# Riden_Wi-Fi_V1_1.net
KiCad netlist of a schematic drawn in EasyEDA
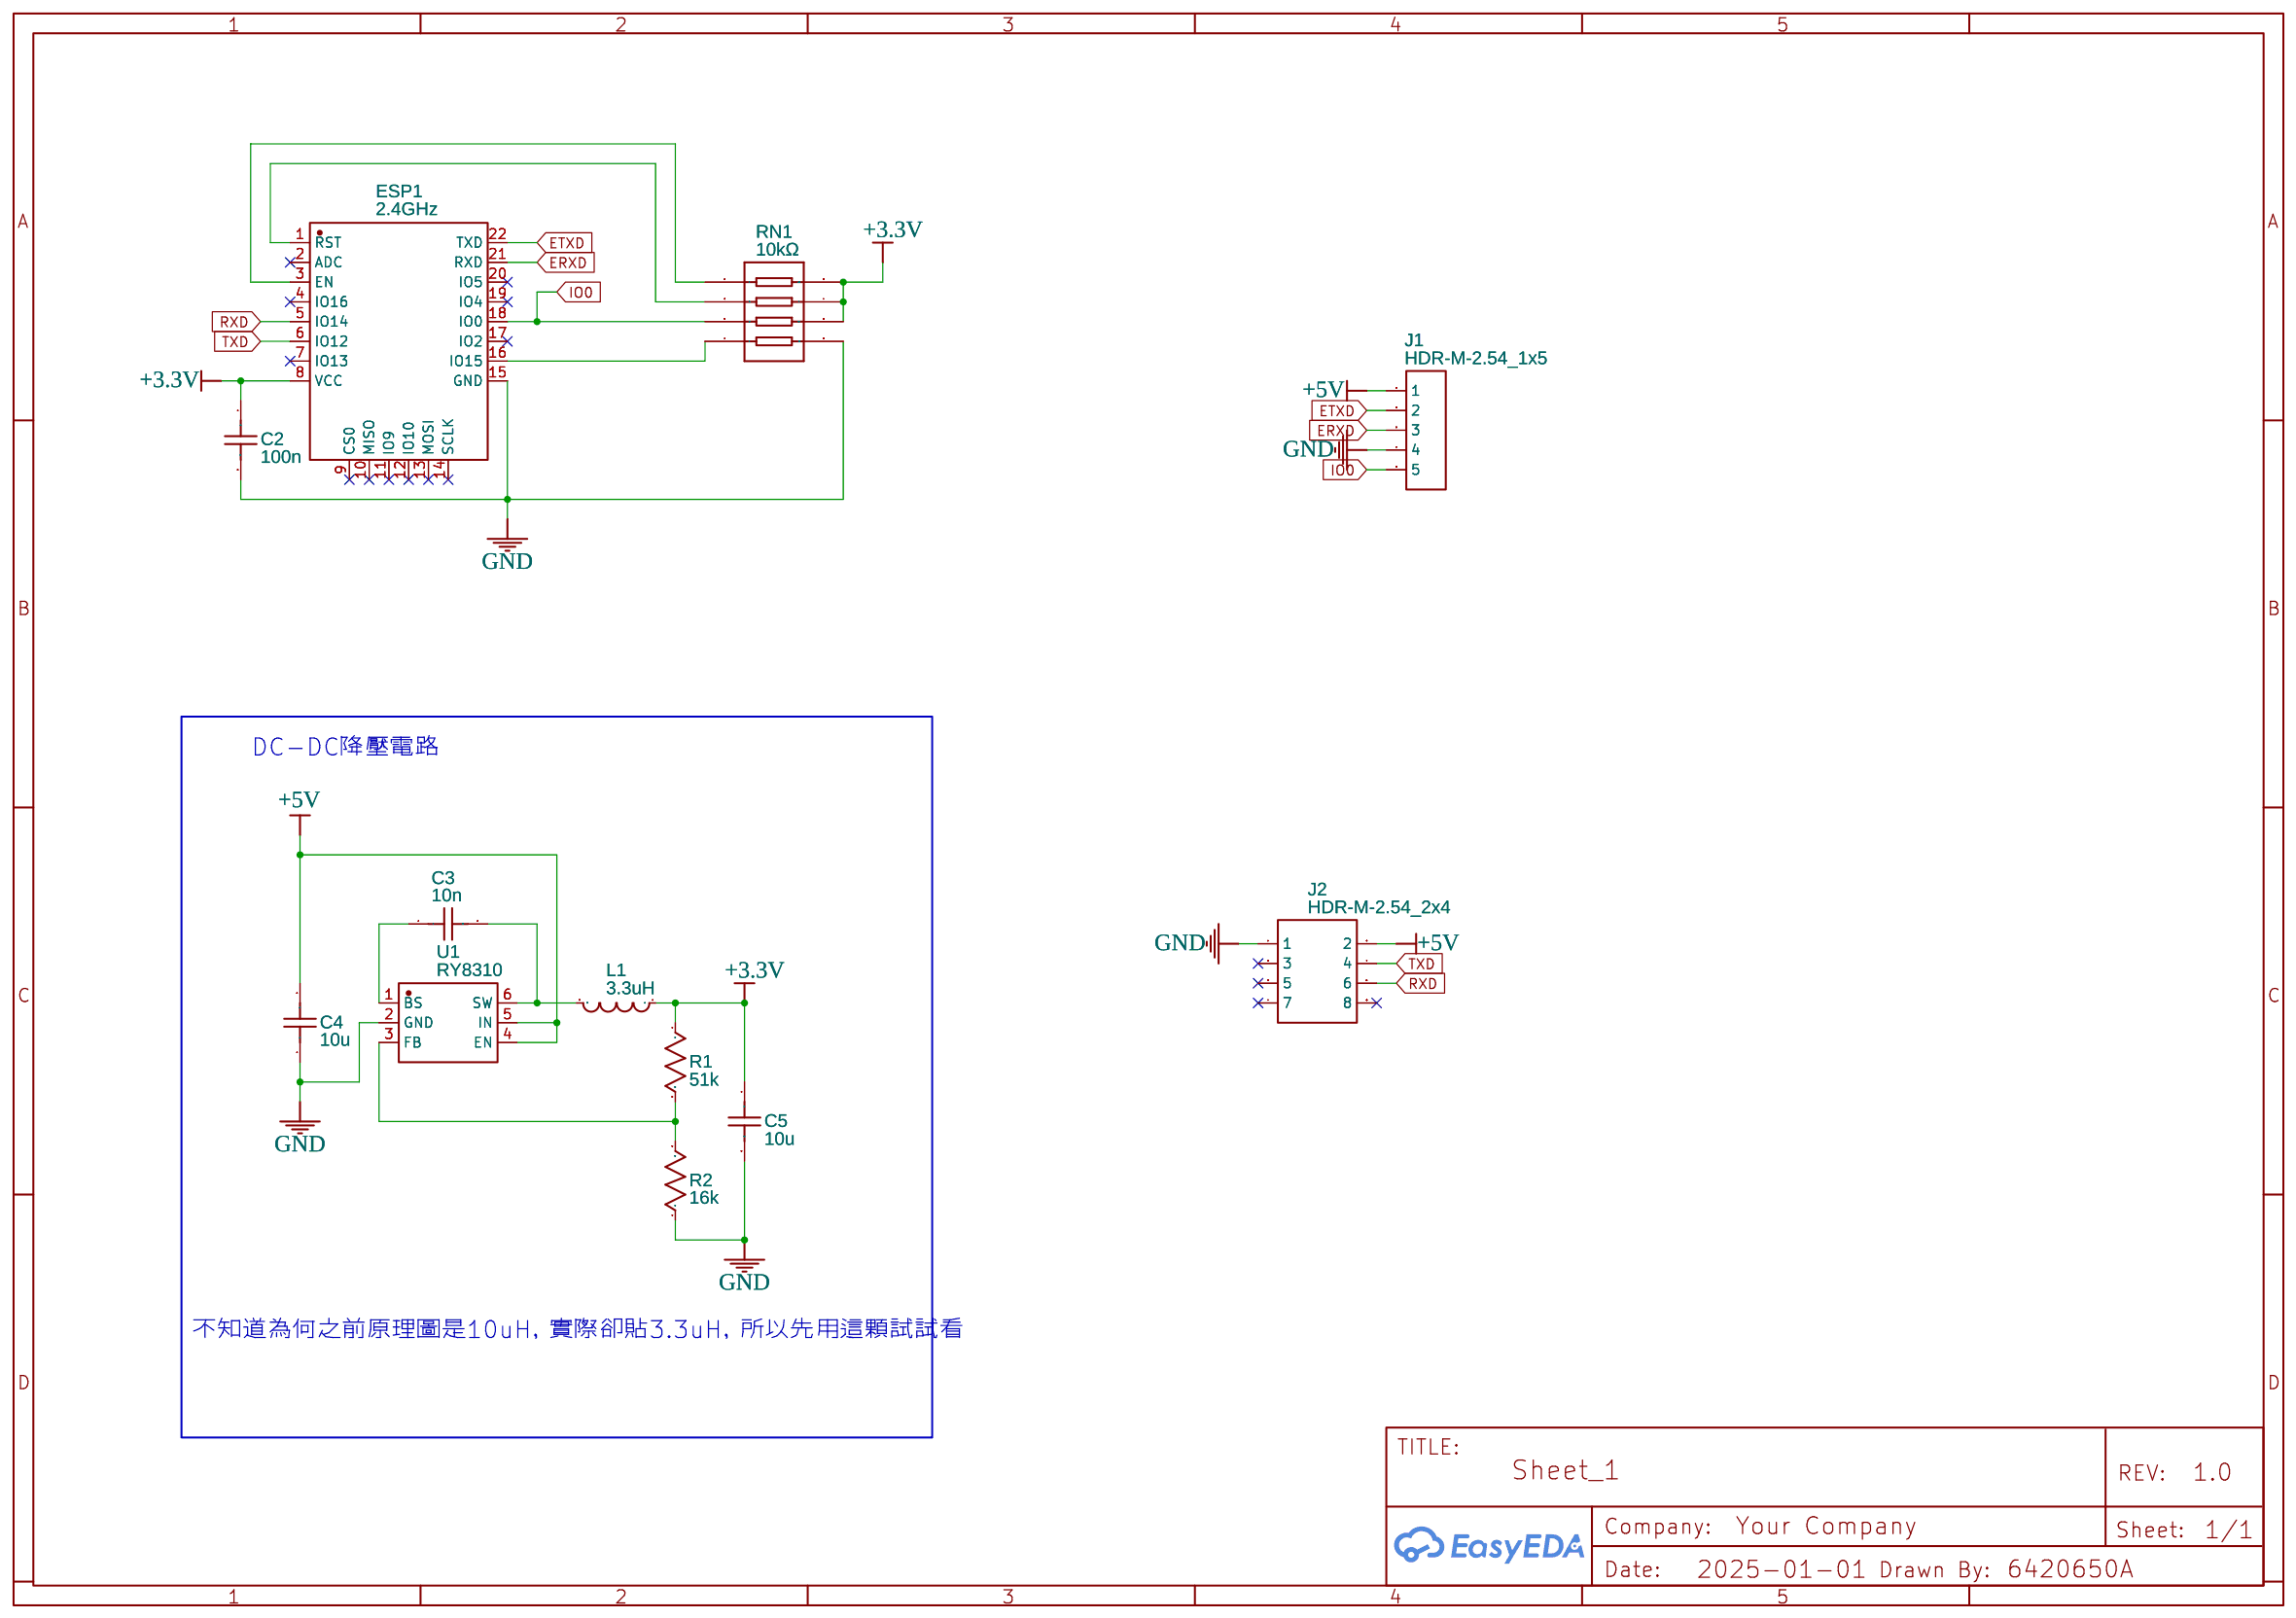
[diagram p0: schematic sheet]

(export (version "E")
  (design (tool "Eeschema 10.0.6"))
  (components
    (comp (ref "C2") (value "100n") (libsource (lib "") (part "C_0603_US_1")))
    (comp (ref "C3") (value "10n") (libsource (lib "") (part "C_0603_US")))
    (comp (ref "C4") (value "10u") (libsource (lib "") (part "C_0603_US_2")))
    (comp (ref "C5") (value "10u") (libsource (lib "") (part "C_0603_US_1")))
    (comp (ref "ESP1")
      (value "2.4GHz")
      (fields (field (name "Manufacturer Part") "ESP-12F") (field (name "Manufacturer") "Ai-Thinker(安信可)"))
      (libsource (lib "") (part "ESP-12F"))
    )
    (comp (ref "J1") (value "HDR-M-2.54_1x5") (libsource (lib "") (part "HDR-M-2.54_1x5")))
    (comp (ref "J2") (value "HDR-M-2.54_2x4") (libsource (lib "") (part "HDR-M-2.54_2x4")))
    (comp (ref "L1")
      (value "3.3uH")
      (fields (field (name "Manufacturer Part") "ASMPM-0806-3R3M-T") (field (name "Manufacturer") "ABRACON"))
      (libsource (lib "") (part "電感_0806"))
    )
    (comp (ref "R1") (value "51k") (libsource (lib "") (part "R_0603_US")))
    (comp (ref "R2") (value "16k") (libsource (lib "") (part "R_0603_US_1")))
    (comp (ref "RN1")
      (value "10kΩ")
      (fields
        (field (name "Manufacturer Part") "4D03WGJ0103T5E")
        (field (name "Manufacturer") "UNI-ROYAL(厚声)")
      )
      (libsource (lib "") (part "排組_0603_4D03WGJ0103T5E"))
    )
    (comp (ref "U1")
      (value "RY8310")
      (fields (field (name "Manufacturer") "RYCHiP(蕊源)"))
      (libsource (lib "") (part "RY8310"))
    )
  )
  (nets
    (net (code "1") (name "+3.3V") (class "Default")
      (node (ref "C2") (pin "1") (pinfunction "1_1") (pintype "unspecified"))
      (node (ref "C5") (pin "1") (pinfunction "1_1") (pintype "unspecified"))
      (node (ref "ESP1") (pin "8") (pinfunction "VCC_8") (pintype "unspecified"))
      (node (ref "L1") (pin "1") (pinfunction "1_1") (pintype "unspecified"))
      (node (ref "R1") (pin "1") (pinfunction "1_1") (pintype "unspecified"))
      (node (ref "RN1") (pin "6") (pinfunction "6_6") (pintype "input"))
      (node (ref "RN1") (pin "7") (pinfunction "7_7") (pintype "input"))
      (node (ref "RN1") (pin "8") (pinfunction "8_8") (pintype "input"))
    )
    (net (code "2") (name "+5V") (class "Default")
      (node (ref "C4") (pin "2") (pinfunction "2_2") (pintype "unspecified"))
      (node (ref "J1") (pin "1") (pinfunction "1_1") (pintype "unspecified"))
      (node (ref "J2") (pin "2") (pinfunction "2_2") (pintype "unspecified"))
      (node (ref "U1") (pin "4") (pinfunction "EN_4") (pintype "unspecified"))
      (node (ref "U1") (pin "5") (pinfunction "IN_5") (pintype "unspecified"))
    )
    (net (code "3") (name "ERXD") (class "Default")
      (node (ref "ESP1") (pin "21") (pinfunction "RXD_21") (pintype "unspecified"))
      (node (ref "J1") (pin "3") (pinfunction "3_3") (pintype "unspecified"))
    )
    (net (code "4") (name "ETXD") (class "Default")
      (node (ref "ESP1") (pin "22") (pinfunction "TXD_22") (pintype "unspecified"))
      (node (ref "J1") (pin "2") (pinfunction "2_2") (pintype "unspecified"))
    )
    (net (code "5") (name "GND") (class "Default")
      (node (ref "C2") (pin "2") (pinfunction "2_2") (pintype "unspecified"))
      (node (ref "C4") (pin "1") (pinfunction "1_1") (pintype "unspecified"))
      (node (ref "C5") (pin "2") (pinfunction "2_2") (pintype "unspecified"))
      (node (ref "ESP1") (pin "15") (pinfunction "GND_15") (pintype "unspecified"))
      (node (ref "J1") (pin "4") (pinfunction "4_4") (pintype "unspecified"))
      (node (ref "J2") (pin "1") (pinfunction "1_1") (pintype "unspecified"))
      (node (ref "R2") (pin "1") (pinfunction "1_1") (pintype "unspecified"))
      (node (ref "RN1") (pin "5") (pinfunction "5_5") (pintype "input"))
      (node (ref "U1") (pin "2") (pinfunction "GND_2") (pintype "unspecified"))
    )
    (net (code "6") (name "IO0") (class "Default")
      (node (ref "ESP1") (pin "18") (pinfunction "IO0_18") (pintype "unspecified"))
      (node (ref "J1") (pin "5") (pinfunction "5_5") (pintype "unspecified"))
      (node (ref "RN1") (pin "3") (pinfunction "3_3") (pintype "input"))
    )
    (net (code "7") (name "Net-(ESP1-EN)") (class "Default")
      (node (ref "ESP1") (pin "3") (pinfunction "EN_3") (pintype "unspecified"))
      (node (ref "RN1") (pin "1") (pinfunction "1_1") (pintype "input"))
    )
    (net (code "8") (name "Net-(ESP1-IO15)") (class "Default")
      (node (ref "ESP1") (pin "16") (pinfunction "IO15_16") (pintype "unspecified"))
      (node (ref "RN1") (pin "4") (pinfunction "4_4") (pintype "input"))
    )
    (net (code "9") (name "Net-(ESP1-RST)") (class "Default")
      (node (ref "ESP1") (pin "1") (pinfunction "RST_1") (pintype "unspecified"))
      (node (ref "RN1") (pin "2") (pinfunction "2_2") (pintype "input"))
    )
    (net (code "10") (name "Net-(U1-BS)") (class "Default")
      (node (ref "C3") (pin "1") (pinfunction "1_1") (pintype "unspecified"))
      (node (ref "U1") (pin "1") (pinfunction "BS_1") (pintype "unspecified"))
    )
    (net (code "11") (name "Net-(U1-FB)") (class "Default")
      (node (ref "R1") (pin "2") (pinfunction "2_2") (pintype "unspecified"))
      (node (ref "R2") (pin "2") (pinfunction "2_2") (pintype "unspecified"))
      (node (ref "U1") (pin "3") (pinfunction "FB_3") (pintype "unspecified"))
    )
    (net (code "12") (name "Net-(U1-SW)") (class "Default")
      (node (ref "C3") (pin "2") (pinfunction "2_2") (pintype "unspecified"))
      (node (ref "L1") (pin "2") (pinfunction "2_2") (pintype "unspecified"))
      (node (ref "U1") (pin "6") (pinfunction "SW_6") (pintype "unspecified"))
    )
    (net (code "13") (name "RXD") (class "Default")
      (node (ref "ESP1") (pin "5") (pinfunction "IO14_5") (pintype "unspecified"))
      (node (ref "J2") (pin "6") (pinfunction "6_6") (pintype "unspecified"))
    )
    (net (code "14") (name "TXD") (class "Default")
      (node (ref "ESP1") (pin "6") (pinfunction "IO12_6") (pintype "unspecified"))
      (node (ref "J2") (pin "4") (pinfunction "4_4") (pintype "unspecified"))
    )
    (net (code "15") (name "unconnected-(ESP1-ADC-Pad2)") (class "Default")
      (node (ref "ESP1") (pin "2") (pinfunction "ADC_2") (pintype "unspecified+no_connect"))
    )
    (net (code "16") (name "unconnected-(ESP1-CS0-Pad9)") (class "Default")
      (node (ref "ESP1") (pin "9") (pinfunction "CS0_9") (pintype "unspecified+no_connect"))
    )
    (net (code "17") (name "unconnected-(ESP1-IO2-Pad17)") (class "Default")
      (node (ref "ESP1") (pin "17") (pinfunction "IO2_17") (pintype "unspecified+no_connect"))
    )
    (net (code "18") (name "unconnected-(ESP1-IO4-Pad19)") (class "Default")
      (node (ref "ESP1") (pin "19") (pinfunction "IO4_19") (pintype "unspecified+no_connect"))
    )
    (net (code "19") (name "unconnected-(ESP1-IO5-Pad20)") (class "Default")
      (node (ref "ESP1") (pin "20") (pinfunction "IO5_20") (pintype "unspecified+no_connect"))
    )
    (net (code "20") (name "unconnected-(ESP1-IO9-Pad11)") (class "Default")
      (node (ref "ESP1") (pin "11") (pinfunction "IO9_11") (pintype "unspecified+no_connect"))
    )
    (net (code "21") (name "unconnected-(ESP1-IO10-Pad12)") (class "Default")
      (node (ref "ESP1") (pin "12") (pinfunction "IO10_12") (pintype "unspecified+no_connect"))
    )
    (net (code "22") (name "unconnected-(ESP1-IO13-Pad7)") (class "Default")
      (node (ref "ESP1") (pin "7") (pinfunction "IO13_7") (pintype "unspecified+no_connect"))
    )
    (net (code "23") (name "unconnected-(ESP1-IO16-Pad4)") (class "Default")
      (node (ref "ESP1") (pin "4") (pinfunction "IO16_4") (pintype "unspecified+no_connect"))
    )
    (net (code "24") (name "unconnected-(ESP1-MISO-Pad10)") (class "Default")
      (node (ref "ESP1") (pin "10") (pinfunction "MISO_10") (pintype "unspecified+no_connect"))
    )
    (net (code "25") (name "unconnected-(ESP1-MOSI-Pad13)") (class "Default")
      (node (ref "ESP1") (pin "13") (pinfunction "MOSI_13") (pintype "unspecified+no_connect"))
    )
    (net (code "26") (name "unconnected-(ESP1-SCLK-Pad14)") (class "Default")
      (node (ref "ESP1") (pin "14") (pinfunction "SCLK_14") (pintype "unspecified+no_connect"))
    )
    (net (code "27") (name "unconnected-(J2-Pad3)") (class "Default")
      (node (ref "J2") (pin "3") (pinfunction "3_3") (pintype "unspecified+no_connect"))
    )
    (net (code "28") (name "unconnected-(J2-Pad5)") (class "Default")
      (node (ref "J2") (pin "5") (pinfunction "5_5") (pintype "unspecified+no_connect"))
    )
    (net (code "29") (name "unconnected-(J2-Pad7)") (class "Default")
      (node (ref "J2") (pin "7") (pinfunction "7_7") (pintype "unspecified+no_connect"))
    )
    (net (code "30") (name "unconnected-(J2-Pad8)") (class "Default")
      (node (ref "J2") (pin "8") (pinfunction "8_8") (pintype "unspecified+no_connect"))
    )
  )
)
